# untitled-Lite.net
KiCad netlist of a schematic drawn in EAGLE
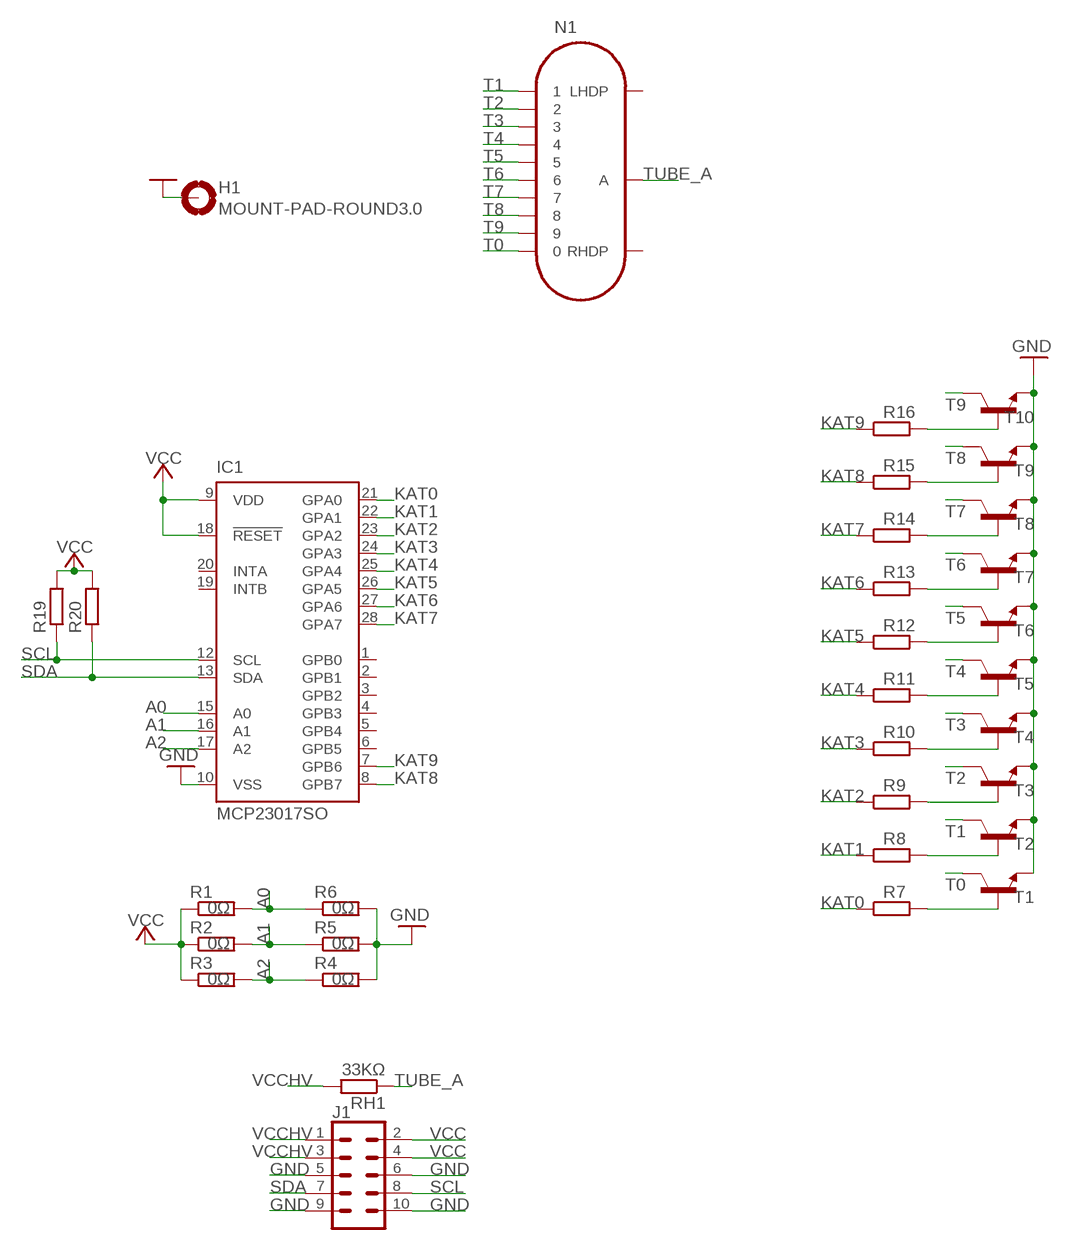
[diagram p0: schematic, sheet 1]

(export (version "E")
  (design (tool "Eeschema 10.0.6"))
  (components
    (comp (ref "H1")
      (value "MOUNT-PAD-ROUND3.0")
      (footprint "eagle-import:3,0-PAD")
      (libsource (lib "eagle-import") (part "MOUNT-PAD-ROUND3.0"))
    )
    (comp (ref "IC1")
      (value "MCP23017SO")
      (footprint "eagle-import:SO28W")
      (libsource (lib "eagle-import") (part "MCP23017SO"))
    )
    (comp (ref "J1")
      (value "CONN_05X2PTH")
      (footprint "eagle-import:2X5")
      (libsource (lib "eagle-import") (part "CONN_05X2PTH"))
    )
    (comp (ref "N1")
      (value "IN-14")
      (footprint "eagle-import:IN-14")
      (libsource (lib "eagle-import") (part "IN-14"))
    )
    (comp (ref "R1")
      (value "0Ω")
      (footprint "eagle-import:R1206")
      (libsource (lib "eagle-import") (part "R-EU_R1206"))
    )
    (comp (ref "R2")
      (value "0Ω")
      (footprint "eagle-import:R1206")
      (libsource (lib "eagle-import") (part "R-EU_R1206"))
    )
    (comp (ref "R3")
      (value "0Ω")
      (footprint "eagle-import:R1206")
      (libsource (lib "eagle-import") (part "R-EU_R1206"))
    )
    (comp (ref "R4")
      (value "0Ω")
      (footprint "eagle-import:R1206")
      (libsource (lib "eagle-import") (part "R-EU_R1206"))
    )
    (comp (ref "R5")
      (value "0Ω")
      (footprint "eagle-import:R1206")
      (libsource (lib "eagle-import") (part "R-EU_R1206"))
    )
    (comp (ref "R6")
      (value "0Ω")
      (footprint "eagle-import:R1206")
      (libsource (lib "eagle-import") (part "R-EU_R1206"))
    )
    (comp (ref "R7")
      (value "R-EU_R1206")
      (footprint "eagle-import:R1206")
      (libsource (lib "eagle-import") (part "R-EU_R1206"))
    )
    (comp (ref "R8")
      (value "R-EU_R1206")
      (footprint "eagle-import:R1206")
      (libsource (lib "eagle-import") (part "R-EU_R1206"))
    )
    (comp (ref "R9")
      (value "R-EU_R1206")
      (footprint "eagle-import:R1206")
      (libsource (lib "eagle-import") (part "R-EU_R1206"))
    )
    (comp (ref "R10")
      (value "R-EU_R1206")
      (footprint "eagle-import:R1206")
      (libsource (lib "eagle-import") (part "R-EU_R1206"))
    )
    (comp (ref "R11")
      (value "R-EU_R1206")
      (footprint "eagle-import:R1206")
      (libsource (lib "eagle-import") (part "R-EU_R1206"))
    )
    (comp (ref "R12")
      (value "R-EU_R1206")
      (footprint "eagle-import:R1206")
      (libsource (lib "eagle-import") (part "R-EU_R1206"))
    )
    (comp (ref "R13")
      (value "R-EU_R1206")
      (footprint "eagle-import:R1206")
      (libsource (lib "eagle-import") (part "R-EU_R1206"))
    )
    (comp (ref "R14")
      (value "R-EU_R1206")
      (footprint "eagle-import:R1206")
      (libsource (lib "eagle-import") (part "R-EU_R1206"))
    )
    (comp (ref "R15")
      (value "R-EU_R1206")
      (footprint "eagle-import:R1206")
      (libsource (lib "eagle-import") (part "R-EU_R1206"))
    )
    (comp (ref "R16")
      (value "R-EU_R1206")
      (footprint "eagle-import:R1206")
      (libsource (lib "eagle-import") (part "R-EU_R1206"))
    )
    (comp (ref "R19")
      (value "R-EU_R1206")
      (footprint "eagle-import:R1206")
      (libsource (lib "eagle-import") (part "R-EU_R1206"))
    )
    (comp (ref "R20")
      (value "R-EU_R1206")
      (footprint "eagle-import:R1206")
      (libsource (lib "eagle-import") (part "R-EU_R1206"))
    )
    (comp (ref "RH1")
      (value "33KΩ")
      (footprint "eagle-import:0207_15")
      (libsource (lib "eagle-import") (part "R-EU_0207/15"))
    )
    (comp (ref "T1")
      (value "MMBTA42LT1-NPN-SOT23-BEC")
      (footprint "eagle-import:SOT23-BEC")
      (libsource (lib "eagle-import") (part "-NPN-SOT23-BECMMBTA42LT1"))
    )
    (comp (ref "T2")
      (value "MMBTA42LT1-NPN-SOT23-BEC")
      (footprint "eagle-import:SOT23-BEC")
      (libsource (lib "eagle-import") (part "-NPN-SOT23-BECMMBTA42LT1"))
    )
    (comp (ref "T3")
      (value "MMBTA42LT1-NPN-SOT23-BEC")
      (footprint "eagle-import:SOT23-BEC")
      (libsource (lib "eagle-import") (part "-NPN-SOT23-BECMMBTA42LT1"))
    )
    (comp (ref "T4")
      (value "MMBTA42LT1-NPN-SOT23-BEC")
      (footprint "eagle-import:SOT23-BEC")
      (libsource (lib "eagle-import") (part "-NPN-SOT23-BECMMBTA42LT1"))
    )
    (comp (ref "T5")
      (value "MMBTA42LT1-NPN-SOT23-BEC")
      (footprint "eagle-import:SOT23-BEC")
      (libsource (lib "eagle-import") (part "-NPN-SOT23-BECMMBTA42LT1"))
    )
    (comp (ref "T6")
      (value "MMBTA42LT1-NPN-SOT23-BEC")
      (footprint "eagle-import:SOT23-BEC")
      (libsource (lib "eagle-import") (part "-NPN-SOT23-BECMMBTA42LT1"))
    )
    (comp (ref "T7")
      (value "MMBTA42LT1-NPN-SOT23-BEC")
      (footprint "eagle-import:SOT23-BEC")
      (libsource (lib "eagle-import") (part "-NPN-SOT23-BECMMBTA42LT1"))
    )
    (comp (ref "T8")
      (value "MMBTA42LT1-NPN-SOT23-BEC")
      (footprint "eagle-import:SOT23-BEC")
      (libsource (lib "eagle-import") (part "-NPN-SOT23-BECMMBTA42LT1"))
    )
    (comp (ref "T9")
      (value "MMBTA42LT1-NPN-SOT23-BEC")
      (footprint "eagle-import:SOT23-BEC")
      (libsource (lib "eagle-import") (part "-NPN-SOT23-BECMMBTA42LT1"))
    )
    (comp (ref "T10")
      (value "MMBTA42LT1-NPN-SOT23-BEC")
      (footprint "eagle-import:SOT23-BEC")
      (libsource (lib "eagle-import") (part "-NPN-SOT23-BECMMBTA42LT1"))
    )
  )
  (nets
    (net (code "1") (name "/A0") (class "Default")
      (node (ref "IC1") (pin "15") (pinfunction "A0_15") (pintype "input"))
      (node (ref "R1") (pin "2") (pinfunction "2_2") (pintype "passive"))
      (node (ref "R6") (pin "1") (pinfunction "1_1") (pintype "passive"))
    )
    (net (code "2") (name "/A1") (class "Default")
      (node (ref "IC1") (pin "16") (pinfunction "A1_16") (pintype "input"))
      (node (ref "R2") (pin "2") (pinfunction "2_2") (pintype "passive"))
      (node (ref "R5") (pin "1") (pinfunction "1_1") (pintype "passive"))
    )
    (net (code "3") (name "/A2") (class "Default")
      (node (ref "IC1") (pin "17") (pinfunction "A2_17") (pintype "input"))
      (node (ref "R3") (pin "2") (pinfunction "2_2") (pintype "passive"))
      (node (ref "R4") (pin "1") (pinfunction "1_1") (pintype "passive"))
    )
    (net (code "4") (name "/KAT0") (class "Default")
      (node (ref "IC1") (pin "21") (pinfunction "GPA0_21") (pintype "bidirectional"))
      (node (ref "R7") (pin "1") (pinfunction "1_1") (pintype "passive"))
    )
    (net (code "5") (name "/KAT1") (class "Default")
      (node (ref "IC1") (pin "22") (pinfunction "GPA1_22") (pintype "bidirectional"))
      (node (ref "R8") (pin "1") (pinfunction "1_1") (pintype "passive"))
    )
    (net (code "6") (name "/KAT2") (class "Default")
      (node (ref "IC1") (pin "23") (pinfunction "GPA2_23") (pintype "bidirectional"))
      (node (ref "R9") (pin "1") (pinfunction "1_1") (pintype "passive"))
    )
    (net (code "7") (name "/KAT3") (class "Default")
      (node (ref "IC1") (pin "24") (pinfunction "GPA3_24") (pintype "bidirectional"))
      (node (ref "R10") (pin "1") (pinfunction "1_1") (pintype "passive"))
    )
    (net (code "8") (name "/KAT4") (class "Default")
      (node (ref "IC1") (pin "25") (pinfunction "GPA4_25") (pintype "bidirectional"))
      (node (ref "R11") (pin "1") (pinfunction "1_1") (pintype "passive"))
    )
    (net (code "9") (name "/KAT5") (class "Default")
      (node (ref "IC1") (pin "26") (pinfunction "GPA5_26") (pintype "bidirectional"))
      (node (ref "R12") (pin "1") (pinfunction "1_1") (pintype "passive"))
    )
    (net (code "10") (name "/KAT6") (class "Default")
      (node (ref "IC1") (pin "27") (pinfunction "GPA6_27") (pintype "bidirectional"))
      (node (ref "R13") (pin "1") (pinfunction "1_1") (pintype "passive"))
    )
    (net (code "11") (name "/KAT7") (class "Default")
      (node (ref "IC1") (pin "28") (pinfunction "GPA7_28") (pintype "bidirectional"))
      (node (ref "R14") (pin "1") (pinfunction "1_1") (pintype "passive"))
    )
    (net (code "12") (name "/KAT8") (class "Default")
      (node (ref "IC1") (pin "8") (pinfunction "GPB7_8") (pintype "bidirectional"))
      (node (ref "R15") (pin "1") (pinfunction "1_1") (pintype "passive"))
    )
    (net (code "13") (name "/KAT9") (class "Default")
      (node (ref "IC1") (pin "7") (pinfunction "GPB6_7") (pintype "bidirectional"))
      (node (ref "R16") (pin "1") (pinfunction "1_1") (pintype "passive"))
    )
    (net (code "14") (name "/SCL") (class "Default")
      (node (ref "IC1") (pin "12") (pinfunction "SCL_12") (pintype "input"))
      (node (ref "J1") (pin "8") (pinfunction "8_8") (pintype "passive"))
      (node (ref "R19") (pin "1") (pinfunction "1_1") (pintype "passive"))
    )
    (net (code "15") (name "/SDA") (class "Default")
      (node (ref "IC1") (pin "13") (pinfunction "SDA_13") (pintype "bidirectional"))
      (node (ref "J1") (pin "7") (pinfunction "7_7") (pintype "passive"))
      (node (ref "R20") (pin "1") (pinfunction "1_1") (pintype "passive"))
    )
    (net (code "16") (name "/T0") (class "Default")
      (node (ref "N1") (pin "0") (pinfunction "0_0") (pintype "bidirectional"))
      (node (ref "T1") (pin "C") (pinfunction "C_C") (pintype "passive"))
    )
    (net (code "17") (name "/T1") (class "Default")
      (node (ref "N1") (pin "1") (pinfunction "1_1") (pintype "bidirectional"))
      (node (ref "T2") (pin "C") (pinfunction "C_C") (pintype "passive"))
    )
    (net (code "18") (name "/T2") (class "Default")
      (node (ref "N1") (pin "2") (pinfunction "2_2") (pintype "bidirectional"))
      (node (ref "T3") (pin "C") (pinfunction "C_C") (pintype "passive"))
    )
    (net (code "19") (name "/T3") (class "Default")
      (node (ref "N1") (pin "3") (pinfunction "3_3") (pintype "bidirectional"))
      (node (ref "T4") (pin "C") (pinfunction "C_C") (pintype "passive"))
    )
    (net (code "20") (name "/T4") (class "Default")
      (node (ref "N1") (pin "4") (pinfunction "4_4") (pintype "bidirectional"))
      (node (ref "T5") (pin "C") (pinfunction "C_C") (pintype "passive"))
    )
    (net (code "21") (name "/T5") (class "Default")
      (node (ref "N1") (pin "5") (pinfunction "5_5") (pintype "bidirectional"))
      (node (ref "T6") (pin "C") (pinfunction "C_C") (pintype "passive"))
    )
    (net (code "22") (name "/T6") (class "Default")
      (node (ref "N1") (pin "6") (pinfunction "6_6") (pintype "bidirectional"))
      (node (ref "T7") (pin "C") (pinfunction "C_C") (pintype "passive"))
    )
    (net (code "23") (name "/T7") (class "Default")
      (node (ref "N1") (pin "7") (pinfunction "7_7") (pintype "bidirectional"))
      (node (ref "T8") (pin "C") (pinfunction "C_C") (pintype "passive"))
    )
    (net (code "24") (name "/T8") (class "Default")
      (node (ref "N1") (pin "8") (pinfunction "8_8") (pintype "bidirectional"))
      (node (ref "T9") (pin "C") (pinfunction "C_C") (pintype "passive"))
    )
    (net (code "25") (name "/T9") (class "Default")
      (node (ref "N1") (pin "9") (pinfunction "9_9") (pintype "bidirectional"))
      (node (ref "T10") (pin "C") (pinfunction "C_C") (pintype "passive"))
    )
    (net (code "26") (name "/TUBE_A") (class "Default")
      (node (ref "N1") (pin "A") (pinfunction "A_A") (pintype "bidirectional"))
      (node (ref "RH1") (pin "1") (pinfunction "1_1") (pintype "passive"))
    )
    (net (code "27") (name "/VCCHV") (class "Default")
      (node (ref "J1") (pin "1") (pinfunction "1_1") (pintype "passive"))
      (node (ref "J1") (pin "3") (pinfunction "3_3") (pintype "passive"))
      (node (ref "RH1") (pin "2") (pinfunction "2_2") (pintype "passive"))
    )
    (net (code "28") (name "GND") (class "Default")
      (node (ref "H1") (pin "B3,0") (pinfunction "MOUNT_B3,0") (pintype "passive"))
      (node (ref "IC1") (pin "10") (pinfunction "VSS_10") (pintype "power_in"))
      (node (ref "J1") (pin "10") (pinfunction "10_10") (pintype "passive"))
      (node (ref "J1") (pin "5") (pinfunction "5_5") (pintype "passive"))
      (node (ref "J1") (pin "6") (pinfunction "6_6") (pintype "passive"))
      (node (ref "J1") (pin "9") (pinfunction "9_9") (pintype "passive"))
      (node (ref "R4") (pin "2") (pinfunction "2_2") (pintype "passive"))
      (node (ref "R5") (pin "2") (pinfunction "2_2") (pintype "passive"))
      (node (ref "R6") (pin "2") (pinfunction "2_2") (pintype "passive"))
      (node (ref "T1") (pin "E") (pinfunction "E_E") (pintype "passive"))
      (node (ref "T10") (pin "E") (pinfunction "E_E") (pintype "passive"))
      (node (ref "T2") (pin "E") (pinfunction "E_E") (pintype "passive"))
      (node (ref "T3") (pin "E") (pinfunction "E_E") (pintype "passive"))
      (node (ref "T4") (pin "E") (pinfunction "E_E") (pintype "passive"))
      (node (ref "T5") (pin "E") (pinfunction "E_E") (pintype "passive"))
      (node (ref "T6") (pin "E") (pinfunction "E_E") (pintype "passive"))
      (node (ref "T7") (pin "E") (pinfunction "E_E") (pintype "passive"))
      (node (ref "T8") (pin "E") (pinfunction "E_E") (pintype "passive"))
      (node (ref "T9") (pin "E") (pinfunction "E_E") (pintype "passive"))
    )
    (net (code "29") (name "Net-(R7-Pad2)") (class "Default")
      (node (ref "R7") (pin "2") (pinfunction "2_2") (pintype "passive"))
      (node (ref "T1") (pin "B") (pinfunction "B_B") (pintype "passive"))
    )
    (net (code "30") (name "Net-(R8-Pad2)") (class "Default")
      (node (ref "R8") (pin "2") (pinfunction "2_2") (pintype "passive"))
      (node (ref "T2") (pin "B") (pinfunction "B_B") (pintype "passive"))
    )
    (net (code "31") (name "Net-(R9-Pad2)") (class "Default")
      (node (ref "R9") (pin "2") (pinfunction "2_2") (pintype "passive"))
      (node (ref "T3") (pin "B") (pinfunction "B_B") (pintype "passive"))
    )
    (net (code "32") (name "Net-(R10-Pad2)") (class "Default")
      (node (ref "R10") (pin "2") (pinfunction "2_2") (pintype "passive"))
      (node (ref "T4") (pin "B") (pinfunction "B_B") (pintype "passive"))
    )
    (net (code "33") (name "Net-(R11-Pad2)") (class "Default")
      (node (ref "R11") (pin "2") (pinfunction "2_2") (pintype "passive"))
      (node (ref "T5") (pin "B") (pinfunction "B_B") (pintype "passive"))
    )
    (net (code "34") (name "Net-(R12-Pad2)") (class "Default")
      (node (ref "R12") (pin "2") (pinfunction "2_2") (pintype "passive"))
      (node (ref "T6") (pin "B") (pinfunction "B_B") (pintype "passive"))
    )
    (net (code "35") (name "Net-(R13-Pad2)") (class "Default")
      (node (ref "R13") (pin "2") (pinfunction "2_2") (pintype "passive"))
      (node (ref "T7") (pin "B") (pinfunction "B_B") (pintype "passive"))
    )
    (net (code "36") (name "Net-(R14-Pad2)") (class "Default")
      (node (ref "R14") (pin "2") (pinfunction "2_2") (pintype "passive"))
      (node (ref "T8") (pin "B") (pinfunction "B_B") (pintype "passive"))
    )
    (net (code "37") (name "Net-(R15-Pad2)") (class "Default")
      (node (ref "R15") (pin "2") (pinfunction "2_2") (pintype "passive"))
      (node (ref "T9") (pin "B") (pinfunction "B_B") (pintype "passive"))
    )
    (net (code "38") (name "Net-(R16-Pad2)") (class "Default")
      (node (ref "R16") (pin "2") (pinfunction "2_2") (pintype "passive"))
      (node (ref "T10") (pin "B") (pinfunction "B_B") (pintype "passive"))
    )
    (net (code "39") (name "VCC") (class "Default")
      (node (ref "IC1") (pin "18") (pinfunction "~{RESET}_18") (pintype "input"))
      (node (ref "IC1") (pin "9") (pinfunction "VDD_9") (pintype "power_in"))
      (node (ref "J1") (pin "2") (pinfunction "2_2") (pintype "passive"))
      (node (ref "J1") (pin "4") (pinfunction "4_4") (pintype "passive"))
      (node (ref "R1") (pin "1") (pinfunction "1_1") (pintype "passive"))
      (node (ref "R19") (pin "2") (pinfunction "2_2") (pintype "passive"))
      (node (ref "R2") (pin "1") (pinfunction "1_1") (pintype "passive"))
      (node (ref "R20") (pin "2") (pinfunction "2_2") (pintype "passive"))
      (node (ref "R3") (pin "1") (pinfunction "1_1") (pintype "passive"))
    )
    (net (code "40") (name "unconnected-(IC1-GPB0-Pad1)") (class "Default")
      (node (ref "IC1") (pin "1") (pinfunction "GPB0_1") (pintype "bidirectional"))
    )
    (net (code "41") (name "unconnected-(IC1-GPB1-Pad2)") (class "Default")
      (node (ref "IC1") (pin "2") (pinfunction "GPB1_2") (pintype "bidirectional"))
    )
    (net (code "42") (name "unconnected-(IC1-GPB2-Pad3)") (class "Default")
      (node (ref "IC1") (pin "3") (pinfunction "GPB2_3") (pintype "bidirectional"))
    )
    (net (code "43") (name "unconnected-(IC1-GPB3-Pad4)") (class "Default")
      (node (ref "IC1") (pin "4") (pinfunction "GPB3_4") (pintype "bidirectional"))
    )
    (net (code "44") (name "unconnected-(IC1-GPB4-Pad5)") (class "Default")
      (node (ref "IC1") (pin "5") (pinfunction "GPB4_5") (pintype "bidirectional"))
    )
    (net (code "45") (name "unconnected-(IC1-GPB5-Pad6)") (class "Default")
      (node (ref "IC1") (pin "6") (pinfunction "GPB5_6") (pintype "bidirectional"))
    )
    (net (code "46") (name "unconnected-(IC1-INTA-Pad20)") (class "Default")
      (node (ref "IC1") (pin "20") (pinfunction "INTA_20") (pintype "output"))
    )
    (net (code "47") (name "unconnected-(IC1-INTB-Pad19)") (class "Default")
      (node (ref "IC1") (pin "19") (pinfunction "INTB_19") (pintype "output"))
    )
    (net (code "48") (name "unconnected-(N1-PadLHDP)") (class "Default")
      (node (ref "N1") (pin "LHDP") (pinfunction "LHDP_LHDP") (pintype "bidirectional"))
    )
    (net (code "49") (name "unconnected-(N1-PadRHDP)") (class "Default")
      (node (ref "N1") (pin "RHDP") (pinfunction "RHDP_RHDP") (pintype "bidirectional"))
    )
  )
)
